# LCD_MicroSD_Flash.net
KiCad netlist of a schematic drawn in Altium Designer
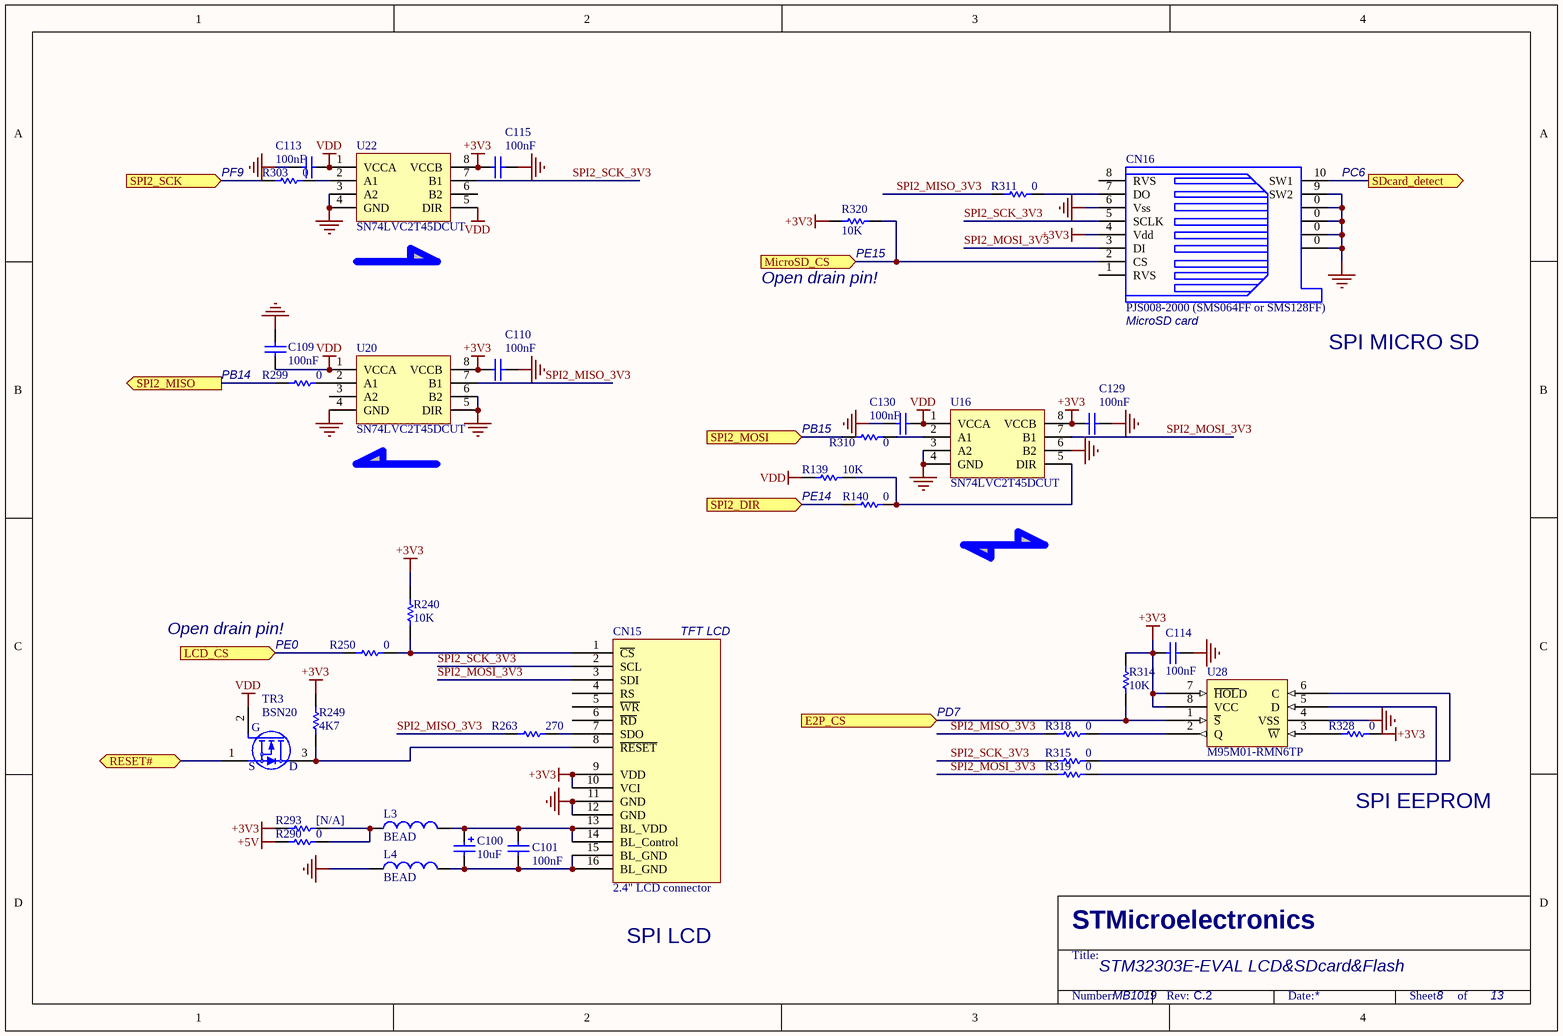
[diagram p0: LCD_MicroSD_Flash.SchDoc]

(export (version "E")
  (design (tool "Eeschema 10.0.6"))
  (components
    (comp (ref "C100")
      (value "10uF")
      (footprint "TAN-A")
      (description "Polarized Capacitor (Radial)")
      (fields (field (name "PUBLISHER") "Altium Limited"))
      (libsource (lib "Miscellaneous Devices") (part "Cap Pol1"))
    )
    (comp (ref "C101")
      (value "100nF")
      (footprint "0603C")
      (description "Capacitor")
      (fields (field (name "PUBLISHER") "Altium Limited"))
      (libsource (lib "Miscellaneous Devices") (part "Cap"))
    )
    (comp (ref "C109")
      (value "100nF")
      (footprint "0603C")
      (description "Capacitor")
      (fields (field (name "PUBLISHER") "Altium Limited"))
      (libsource (lib "Miscellaneous Devices") (part "CAP"))
    )
    (comp (ref "C110")
      (value "100nF")
      (footprint "0603C")
      (description "Capacitor")
      (fields (field (name "PUBLISHER") "Altium Limited"))
      (libsource (lib "Miscellaneous Devices") (part "CAP"))
    )
    (comp (ref "C113")
      (value "100nF")
      (footprint "0603C")
      (description "Capacitor")
      (fields (field (name "PUBLISHER") "Altium Limited"))
      (libsource (lib "Miscellaneous Devices") (part "CAP"))
    )
    (comp (ref "C114")
      (value "100nF")
      (footprint "0603C")
      (description "Capacitor")
      (fields (field (name "PUBLISHER") "Altium Limited"))
      (libsource (lib "Miscellaneous Devices") (part "Cap"))
    )
    (comp (ref "C115")
      (value "100nF")
      (footprint "0603C")
      (description "Capacitor")
      (fields (field (name "PUBLISHER") "Altium Limited"))
      (libsource (lib "Miscellaneous Devices") (part "CAP"))
    )
    (comp (ref "C129")
      (value "100nF")
      (footprint "0603C")
      (description "Capacitor")
      (fields (field (name "PUBLISHER") "Altium Limited"))
      (libsource (lib "Miscellaneous Devices") (part "CAP"))
    )
    (comp (ref "C130")
      (value "100nF")
      (footprint "0603C")
      (description "Capacitor")
      (fields (field (name "PUBLISHER") "Altium Limited"))
      (libsource (lib "Miscellaneous Devices") (part "CAP"))
    )
    (comp (ref "CN15")
      (value "2.4\" LCD connector")
      (footprint "MB895CS")
      (libsource (lib "Manta-edge") (part "ColorLCD_module"))
    )
    (comp (ref "CN16")
      (value "PJS008-2000 (SMS064FF or SMS128FF)")
      (footprint "MSD(PJS008)")
      (libsource (lib "MB525") (part "SMS016AFA5E"))
    )
    (comp (ref "L3")
      (value "BEAD")
      (footprint "0603L")
      (description "Inductor")
      (fields (field (name "PUBLISHER") "Altium Limited"))
      (libsource (lib "Miscellaneous Devices") (part "Inductor"))
    )
    (comp (ref "L4")
      (value "BEAD")
      (footprint "0603L")
      (description "Inductor")
      (fields (field (name "PUBLISHER") "Altium Limited"))
      (libsource (lib "Miscellaneous Devices") (part "Inductor"))
    )
    (comp (ref "R139")
      (value "10K")
      (footprint "0603R")
      (description "Resistor")
      (fields (field (name "PUBLISHER") "Altium Limited"))
      (libsource (lib "Miscellaneous Devices") (part "Res1"))
    )
    (comp (ref "R140")
      (value "0")
      (footprint "0603R")
      (description "Resistor")
      (fields (field (name "PUBLISHER") "Altium Limited"))
      (libsource (lib "Miscellaneous Devices") (part "Res1"))
    )
    (comp (ref "R240")
      (value "10K")
      (footprint "0603R")
      (description "Resistor")
      (fields (field (name "PUBLISHER") "Altium Limited"))
      (libsource (lib "Miscellaneous Devices") (part "Res1"))
    )
    (comp (ref "R249")
      (value "4K7")
      (footprint "0603R")
      (description "Resistor")
      (fields (field (name "PUBLISHER") "Altium Limited"))
      (libsource (lib "Miscellaneous Devices") (part "Res1"))
    )
    (comp (ref "R250")
      (value "0")
      (footprint "0603R")
      (description "Resistor")
      (fields (field (name "PUBLISHER") "Altium Limited"))
      (libsource (lib "Miscellaneous Devices") (part "Res1"))
    )
    (comp (ref "R263")
      (value "270")
      (footprint "0603R")
      (description "Resistor")
      (fields (field (name "PUBLISHER") "Altium Limited"))
      (libsource (lib "Miscellaneous Devices") (part "Res1"))
    )
    (comp (ref "R290")
      (value "0")
      (footprint "0603R")
      (description "Resistor")
      (fields (field (name "PUBLISHER") "Altium Limited"))
      (libsource (lib "Miscellaneous Devices") (part "Res1"))
    )
    (comp (ref "R293")
      (value "[N/A]")
      (footprint "0603R")
      (description "Resistor")
      (fields (field (name "PUBLISHER") "Altium Limited"))
      (libsource (lib "Miscellaneous Devices") (part "Res1"))
    )
    (comp (ref "R299")
      (value "0")
      (footprint "0603R")
      (description "Resistor")
      (fields (field (name "PUBLISHER") "Altium Limited"))
      (libsource (lib "Miscellaneous Devices") (part "Res1"))
    )
    (comp (ref "R303")
      (value "0")
      (footprint "0603R")
      (description "Resistor")
      (fields (field (name "PUBLISHER") "Altium Limited"))
      (libsource (lib "Miscellaneous Devices") (part "res1"))
    )
    (comp (ref "R310")
      (value "0")
      (footprint "0603R")
      (description "Resistor")
      (fields (field (name "PUBLISHER") "Altium Limited"))
      (libsource (lib "Miscellaneous Devices") (part "res1"))
    )
    (comp (ref "R311")
      (value "0")
      (footprint "0603R")
      (description "Resistor")
      (fields (field (name "PUBLISHER") "Altium Limited"))
      (libsource (lib "Miscellaneous Devices") (part "Res1"))
    )
    (comp (ref "R314")
      (value "10K")
      (footprint "0603R")
      (description "Resistor")
      (fields (field (name "PUBLISHER") "Altium Limited"))
      (libsource (lib "Miscellaneous Devices") (part "res1"))
    )
    (comp (ref "R315")
      (value "0")
      (footprint "0603R")
      (description "Resistor")
      (fields (field (name "PUBLISHER") "Altium Limited"))
      (libsource (lib "Miscellaneous Devices") (part "Res1"))
    )
    (comp (ref "R318")
      (value "0")
      (footprint "0603R")
      (description "Resistor")
      (fields (field (name "PUBLISHER") "Altium Limited"))
      (libsource (lib "Miscellaneous Devices") (part "Res1"))
    )
    (comp (ref "R319")
      (value "0")
      (footprint "0603R")
      (description "Resistor")
      (fields (field (name "PUBLISHER") "Altium Limited"))
      (libsource (lib "Miscellaneous Devices") (part "Res1"))
    )
    (comp (ref "R320")
      (value "10K")
      (footprint "0603R")
      (description "Resistor")
      (fields (field (name "PUBLISHER") "Altium Limited"))
      (libsource (lib "Miscellaneous Devices") (part "Res1"))
    )
    (comp (ref "R328")
      (value "0")
      (footprint "0603R")
      (description "Resistor")
      (fields (field (name "PUBLISHER") "Altium Limited"))
      (libsource (lib "Miscellaneous Devices") (part "Res1"))
    )
    (comp (ref "TR3") (value "BSN20") (footprint "SOT-23") (libsource (lib "MB525") (part "2N7000")))
    (comp (ref "U16")
      (value "SN74LVC2T45DCUT")
      (footprint "VSSOP8")
      (libsource (lib "MB818") (part "SN74LVC2T45DCUT"))
    )
    (comp (ref "U20")
      (value "SN74LVC2T45DCUT")
      (footprint "VSSOP8")
      (libsource (lib "MB818") (part "SN74LVC2T45DCUT"))
    )
    (comp (ref "U22")
      (value "SN74LVC2T45DCUT")
      (footprint "VSSOP8")
      (libsource (lib "MB818") (part "SN74LVC2T45DCUT"))
    )
    (comp (ref "U28") (value "M95M01-RMN6TP") (footprint "SO8") (libsource (lib "MB988") (part "M95040-R")))
  )
  (nets
    (net (code "1") (name "+3V3") (class "Default")
      (node (ref "C110") (pin "2") (pinfunction "2_2") (pintype "passive"))
      (node (ref "C114") (pin "1") (pinfunction "1_1") (pintype "passive"))
      (node (ref "C115") (pin "2") (pinfunction "2_2") (pintype "passive"))
      (node (ref "C129") (pin "2") (pinfunction "2_2") (pintype "passive"))
      (node (ref "CN15") (pin "10") (pinfunction "VCI_10") (pintype "passive"))
      (node (ref "CN15") (pin "9") (pinfunction "VDD_9") (pintype "passive"))
      (node (ref "CN16") (pin "4") (pinfunction "Vdd_4") (pintype "passive"))
      (node (ref "R240") (pin "2") (pinfunction "2_2") (pintype "passive"))
      (node (ref "R249") (pin "2") (pinfunction "2_2") (pintype "passive"))
      (node (ref "R293") (pin "1") (pinfunction "1_1") (pintype "passive"))
      (node (ref "R314") (pin "1") (pinfunction "1_1") (pintype "passive"))
      (node (ref "R320") (pin "2") (pinfunction "2_2") (pintype "passive"))
      (node (ref "R328") (pin "1") (pinfunction "1_1") (pintype "passive"))
      (node (ref "U16") (pin "8") (pinfunction "VCCB_8") (pintype "passive"))
      (node (ref "U20") (pin "8") (pinfunction "VCCB_8") (pintype "passive"))
      (node (ref "U22") (pin "8") (pinfunction "VCCB_8") (pintype "passive"))
      (node (ref "U28") (pin "7") (pinfunction "~{HOL}D_7") (pintype "input"))
      (node (ref "U28") (pin "8") (pinfunction "VCC_8") (pintype "power_in"))
    )
    (net (code "2") (name "+5V") (class "Default")
      (node (ref "R290") (pin "1") (pinfunction "1_1") (pintype "passive"))
    )
    (net (code "3") (name "/E2P_CS") (class "Default")
      (node (ref "R314") (pin "2") (pinfunction "2_2") (pintype "passive"))
      (node (ref "U28") (pin "1") (pinfunction "~{S}_1") (pintype "input"))
    )
    (net (code "4") (name "/LCD_CS") (class "Default")
      (node (ref "R250") (pin "1") (pinfunction "1_1") (pintype "passive"))
    )
    (net (code "5") (name "/MicroSD_CS") (class "Default")
      (node (ref "CN16") (pin "2") (pinfunction "CS_2") (pintype "passive"))
      (node (ref "R320") (pin "1") (pinfunction "1_1") (pintype "passive"))
    )
    (net (code "6") (name "/RESET#") (class "Default")
      (node (ref "TR3") (pin "1") (pinfunction "S_1") (pintype "passive"))
    )
    (net (code "7") (name "/SDcard_detect") (class "Default")
      (node (ref "CN16") (pin "10") (pinfunction "SW1_10") (pintype "passive"))
    )
    (net (code "8") (name "/SPI2_DIR") (class "Default")
      (node (ref "R140") (pin "2") (pinfunction "2_2") (pintype "passive"))
    )
    (net (code "9") (name "/SPI2_MISO") (class "Default")
      (node (ref "R299") (pin "1") (pinfunction "1_1") (pintype "passive"))
    )
    (net (code "10") (name "/SPI2_MISO_3V3") (class "Default")
      (node (ref "R263") (pin "1") (pinfunction "1_1") (pintype "passive"))
      (node (ref "R311") (pin "1") (pinfunction "1_1") (pintype "passive"))
      (node (ref "R318") (pin "2") (pinfunction "2_2") (pintype "passive"))
      (node (ref "U20") (pin "7") (pinfunction "B1_7") (pintype "passive"))
    )
    (net (code "11") (name "/SPI2_MOSI") (class "Default")
      (node (ref "R310") (pin "2") (pinfunction "2_2") (pintype "passive"))
    )
    (net (code "12") (name "/SPI2_MOSI_3V3") (class "Default")
      (node (ref "CN15") (pin "3") (pinfunction "SDI_3") (pintype "passive"))
      (node (ref "CN16") (pin "3") (pinfunction "DI_3") (pintype "passive"))
      (node (ref "R319") (pin "2") (pinfunction "2_2") (pintype "passive"))
      (node (ref "U16") (pin "7") (pinfunction "B1_7") (pintype "passive"))
    )
    (net (code "13") (name "/SPI2_SCK") (class "Default")
      (node (ref "R303") (pin "2") (pinfunction "2_2") (pintype "passive"))
    )
    (net (code "14") (name "/SPI2_SCK_3V3") (class "Default")
      (node (ref "CN15") (pin "2") (pinfunction "SCL_2") (pintype "passive"))
      (node (ref "CN16") (pin "5") (pinfunction "SCLK_5") (pintype "passive"))
      (node (ref "R315") (pin "2") (pinfunction "2_2") (pintype "passive"))
      (node (ref "U22") (pin "7") (pinfunction "B1_7") (pintype "passive"))
    )
    (net (code "15") (name "GND") (class "Default")
      (node (ref "C109") (pin "1") (pinfunction "1_1") (pintype "passive"))
      (node (ref "C110") (pin "1") (pinfunction "1_1") (pintype "passive"))
      (node (ref "C113") (pin "1") (pinfunction "1_1") (pintype "passive"))
      (node (ref "C114") (pin "2") (pinfunction "2_2") (pintype "passive"))
      (node (ref "C115") (pin "1") (pinfunction "1_1") (pintype "passive"))
      (node (ref "C129") (pin "1") (pinfunction "1_1") (pintype "passive"))
      (node (ref "C130") (pin "1") (pinfunction "1_1") (pintype "passive"))
      (node (ref "CN15") (pin "11") (pinfunction "GND_11") (pintype "passive"))
      (node (ref "CN15") (pin "12") (pinfunction "GND_12") (pintype "passive"))
      (node (ref "CN16") (pin "0") (pintype "passive"))
      (node (ref "CN16") (pin "6") (pinfunction "Vss_6") (pintype "passive"))
      (node (ref "CN16") (pin "9") (pinfunction "SW2_9") (pintype "passive"))
      (node (ref "L4") (pin "1") (pinfunction "1_1") (pintype "passive"))
      (node (ref "U16") (pin "3") (pinfunction "A2_3") (pintype "passive"))
      (node (ref "U16") (pin "4") (pinfunction "GND_4") (pintype "passive"))
      (node (ref "U16") (pin "6") (pinfunction "B2_6") (pintype "passive"))
      (node (ref "U20") (pin "4") (pinfunction "GND_4") (pintype "passive"))
      (node (ref "U20") (pin "5") (pinfunction "DIR_5") (pintype "passive"))
      (node (ref "U20") (pin "6") (pinfunction "B2_6") (pintype "passive"))
      (node (ref "U22") (pin "3") (pinfunction "A2_3") (pintype "passive"))
      (node (ref "U22") (pin "4") (pinfunction "GND_4") (pintype "passive"))
      (node (ref "U28") (pin "4") (pinfunction "VSS_4") (pintype "power_in"))
    )
    (net (code "16") (name "Net-(C100-Pad2)") (class "Default")
      (node (ref "C100") (pin "2") (pinfunction "2_2") (pintype "passive"))
      (node (ref "C101") (pin "2") (pinfunction "2_2") (pintype "passive"))
      (node (ref "CN15") (pin "15") (pinfunction "BL_GND_15") (pintype "passive"))
      (node (ref "CN15") (pin "16") (pinfunction "BL_GND_16") (pintype "passive"))
      (node (ref "L4") (pin "2") (pinfunction "2_2") (pintype "passive"))
    )
    (net (code "17") (name "Net-(CN15-BL_Control)") (class "Default")
      (node (ref "C100") (pin "1") (pinfunction "1_1") (pintype "passive"))
      (node (ref "C101") (pin "1") (pinfunction "1_1") (pintype "passive"))
      (node (ref "CN15") (pin "13") (pinfunction "BL_VDD_13") (pintype "passive"))
      (node (ref "CN15") (pin "14") (pinfunction "BL_Control_14") (pintype "passive"))
      (node (ref "L3") (pin "2") (pinfunction "2_2") (pintype "passive"))
    )
    (net (code "18") (name "Net-(CN15-SDO)") (class "Default")
      (node (ref "CN15") (pin "7") (pinfunction "SDO_7") (pintype "passive"))
      (node (ref "R263") (pin "2") (pinfunction "2_2") (pintype "passive"))
    )
    (net (code "19") (name "Net-(CN15-~{CS})") (class "Default")
      (node (ref "CN15") (pin "1") (pinfunction "~{CS}_1") (pintype "passive"))
      (node (ref "R240") (pin "1") (pinfunction "1_1") (pintype "passive"))
      (node (ref "R250") (pin "2") (pinfunction "2_2") (pintype "passive"))
    )
    (net (code "20") (name "Net-(CN15-~{RESET})") (class "Default")
      (node (ref "CN15") (pin "8") (pinfunction "~{RESET}_8") (pintype "passive"))
      (node (ref "R249") (pin "1") (pinfunction "1_1") (pintype "passive"))
      (node (ref "TR3") (pin "3") (pinfunction "D_3") (pintype "passive"))
    )
    (net (code "21") (name "Net-(CN16-DO)") (class "Default")
      (node (ref "CN16") (pin "7") (pinfunction "DO_7") (pintype "passive"))
      (node (ref "R311") (pin "2") (pinfunction "2_2") (pintype "passive"))
    )
    (net (code "22") (name "Net-(L3-Pad1)") (class "Default")
      (node (ref "L3") (pin "1") (pinfunction "1_1") (pintype "passive"))
      (node (ref "R290") (pin "2") (pinfunction "2_2") (pintype "passive"))
      (node (ref "R293") (pin "2") (pinfunction "2_2") (pintype "passive"))
    )
    (net (code "23") (name "Net-(U16-A1)") (class "Default")
      (node (ref "R310") (pin "1") (pinfunction "1_1") (pintype "passive"))
      (node (ref "U16") (pin "2") (pinfunction "A1_2") (pintype "passive"))
    )
    (net (code "24") (name "Net-(U16-DIR)") (class "Default")
      (node (ref "R139") (pin "1") (pinfunction "1_1") (pintype "passive"))
      (node (ref "R140") (pin "1") (pinfunction "1_1") (pintype "passive"))
      (node (ref "U16") (pin "5") (pinfunction "DIR_5") (pintype "passive"))
    )
    (net (code "25") (name "Net-(U20-A1)") (class "Default")
      (node (ref "R299") (pin "2") (pinfunction "2_2") (pintype "passive"))
      (node (ref "U20") (pin "2") (pinfunction "A1_2") (pintype "passive"))
    )
    (net (code "26") (name "Net-(U22-A1)") (class "Default")
      (node (ref "R303") (pin "1") (pinfunction "1_1") (pintype "passive"))
      (node (ref "U22") (pin "2") (pinfunction "A1_2") (pintype "passive"))
    )
    (net (code "27") (name "Net-(U28-C)") (class "Default")
      (node (ref "R315") (pin "1") (pinfunction "1_1") (pintype "passive"))
      (node (ref "U28") (pin "6") (pinfunction "C_6") (pintype "input"))
    )
    (net (code "28") (name "Net-(U28-D)") (class "Default")
      (node (ref "R319") (pin "1") (pinfunction "1_1") (pintype "passive"))
      (node (ref "U28") (pin "5") (pinfunction "D_5") (pintype "input"))
    )
    (net (code "29") (name "Net-(U28-Q)") (class "Default")
      (node (ref "R318") (pin "1") (pinfunction "1_1") (pintype "passive"))
      (node (ref "U28") (pin "2") (pinfunction "Q_2") (pintype "output"))
    )
    (net (code "30") (name "Net-(U28-~{W})") (class "Default")
      (node (ref "R328") (pin "2") (pinfunction "2_2") (pintype "passive"))
      (node (ref "U28") (pin "3") (pinfunction "~{W}_3") (pintype "input"))
    )
    (net (code "31") (name "VDD") (class "Default")
      (node (ref "C109") (pin "2") (pinfunction "2_2") (pintype "passive"))
      (node (ref "C113") (pin "2") (pinfunction "2_2") (pintype "passive"))
      (node (ref "C130") (pin "2") (pinfunction "2_2") (pintype "passive"))
      (node (ref "R139") (pin "2") (pinfunction "2_2") (pintype "passive"))
      (node (ref "TR3") (pin "2") (pinfunction "G_2") (pintype "passive"))
      (node (ref "U16") (pin "1") (pinfunction "VCCA_1") (pintype "passive"))
      (node (ref "U20") (pin "1") (pinfunction "VCCA_1") (pintype "passive"))
      (node (ref "U22") (pin "1") (pinfunction "VCCA_1") (pintype "passive"))
      (node (ref "U22") (pin "5") (pinfunction "DIR_5") (pintype "passive"))
    )
    (net (code "32") (name "unconnected-(CN15-RS-Pad4)") (class "Default")
      (node (ref "CN15") (pin "4") (pinfunction "RS_4") (pintype "passive"))
    )
    (net (code "33") (name "unconnected-(CN15-~{RD}-Pad6)") (class "Default")
      (node (ref "CN15") (pin "6") (pinfunction "~{RD}_6") (pintype "passive"))
    )
    (net (code "34") (name "unconnected-(CN15-~{WR}-Pad5)") (class "Default")
      (node (ref "CN15") (pin "5") (pinfunction "~{WR}_5") (pintype "passive"))
    )
    (net (code "35") (name "unconnected-(CN16-RVS-Pad1)") (class "Default")
      (node (ref "CN16") (pin "1") (pinfunction "RVS_1") (pintype "passive"))
    )
    (net (code "36") (name "unconnected-(CN16-RVS-Pad8)") (class "Default")
      (node (ref "CN16") (pin "8") (pinfunction "RVS_8") (pintype "passive"))
    )
    (net (code "37") (name "unconnected-(U20-A2-Pad3)") (class "Default")
      (node (ref "U20") (pin "3") (pinfunction "A2_3") (pintype "passive"))
    )
    (net (code "38") (name "unconnected-(U22-B2-Pad6)") (class "Default")
      (node (ref "U22") (pin "6") (pinfunction "B2_6") (pintype "passive"))
    )
  )
)
